# untitled.net
KiCad netlist of a schematic drawn in EAGLE
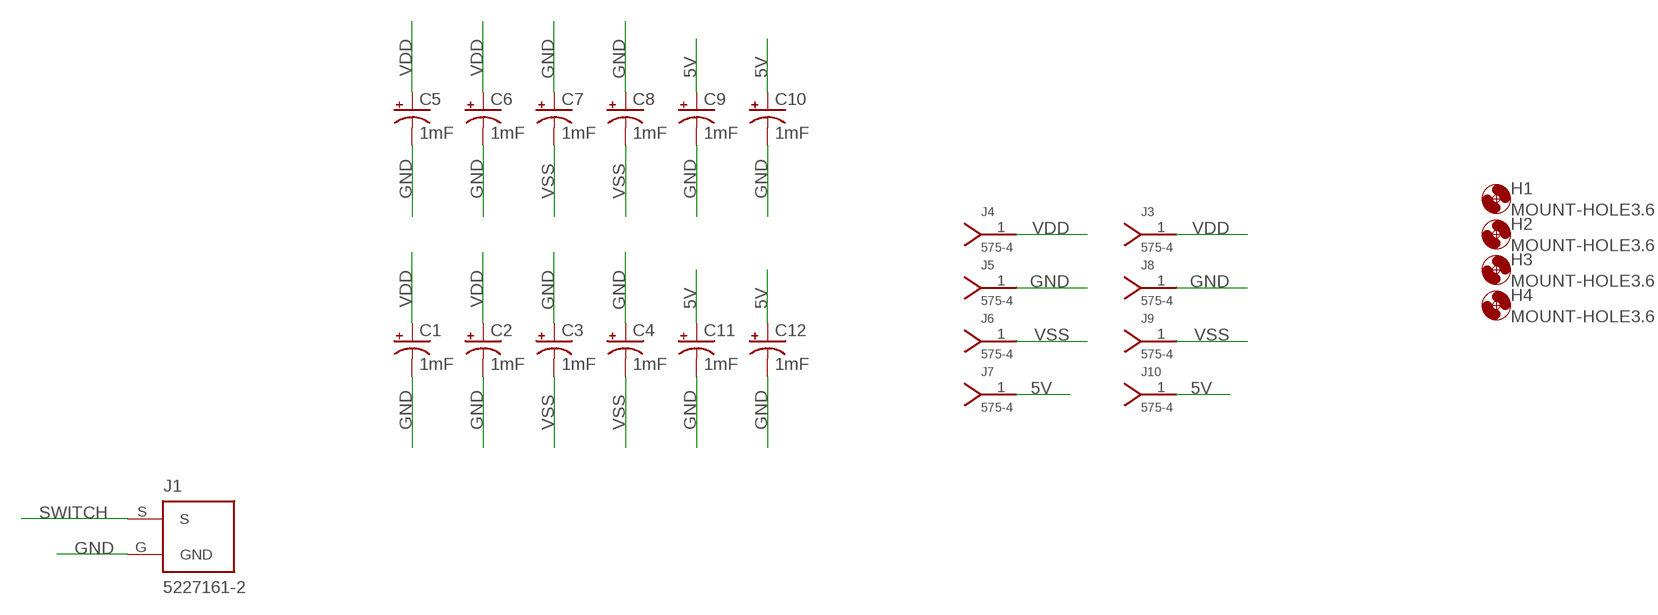
[diagram p0: schematic, sheet 1]
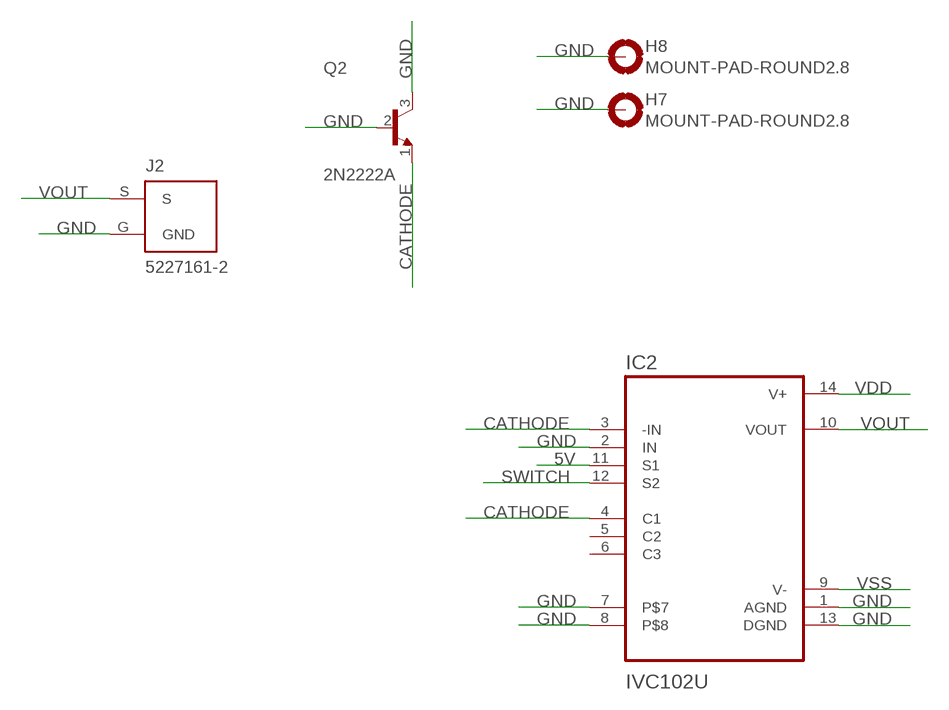
[diagram p1: schematic, sheet 2]
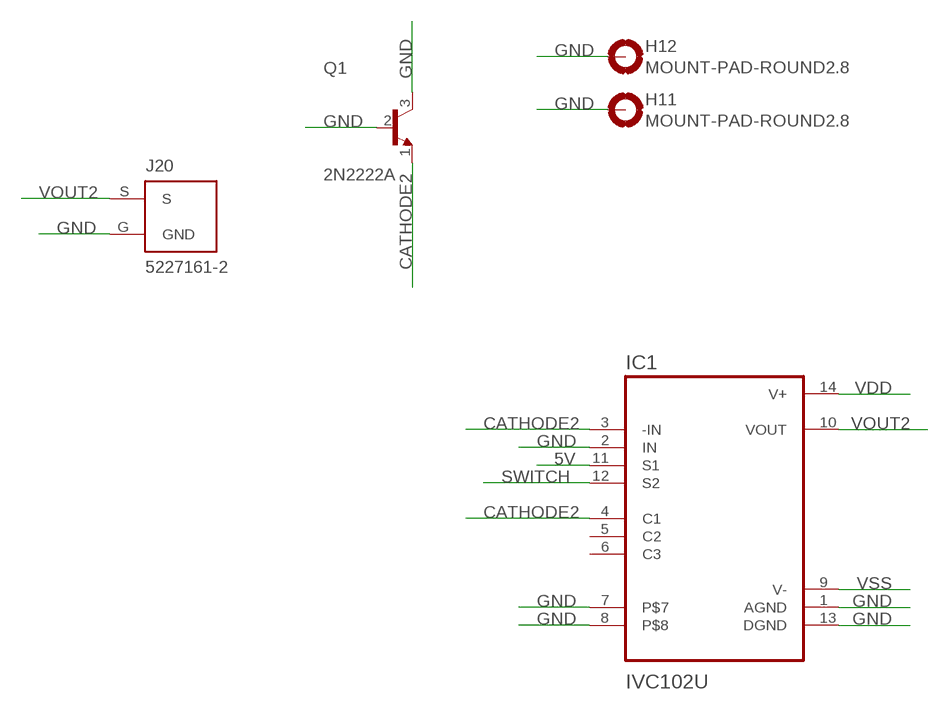
[diagram p2: schematic, sheet 3]
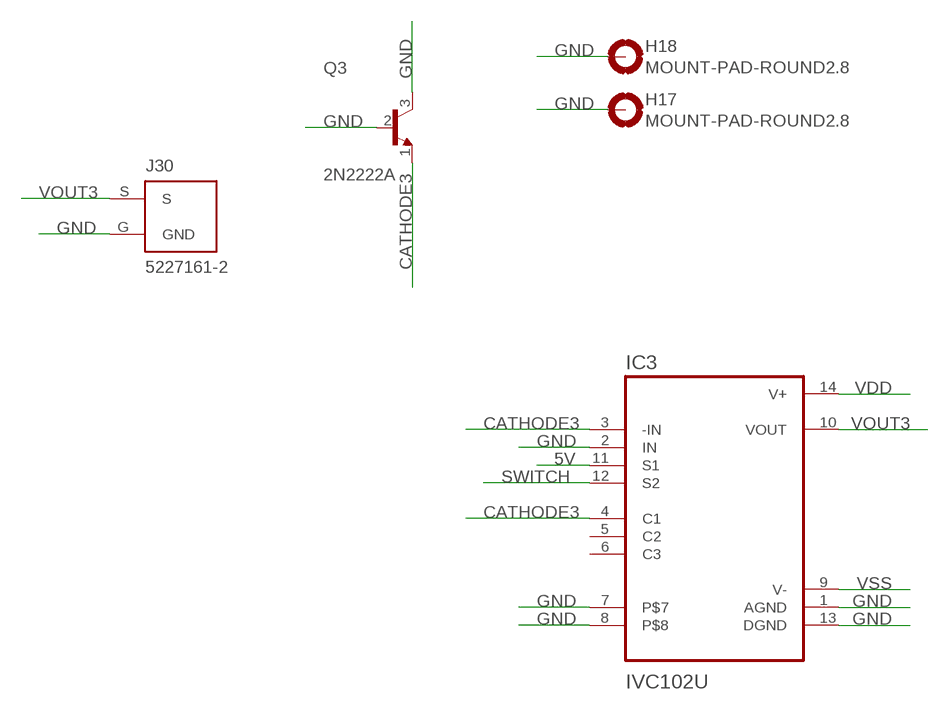
[diagram p3: schematic, sheet 4]
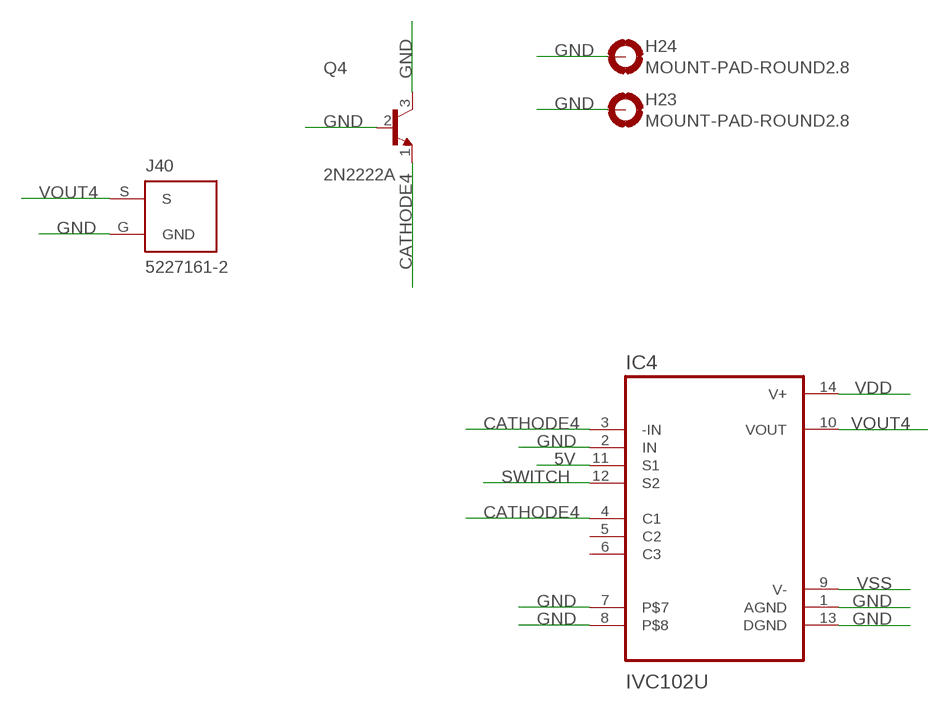
[diagram p4: schematic, sheet 5]

(export (version "E")
  (design (tool "Eeschema 10.0.6"))
  (components
    (comp (ref "H17")
      (value "MOUNT-PAD-ROUND2.8")
      (footprint "eagle-import:2,8-PAD")
      (libsource (lib "eagle-import") (part "MOUNT-PAD-ROUND2.8"))
    )
    (comp (ref "H18")
      (value "MOUNT-PAD-ROUND2.8")
      (footprint "eagle-import:2,8-PAD")
      (libsource (lib "eagle-import") (part "MOUNT-PAD-ROUND2.8"))
    )
    (comp (ref "IC3")
      (value "IVC102U")
      (footprint "eagle-import:SOIC127P600X175-14N")
      (fields (field (name "MF") "Texas"))
      (libsource (lib "eagle-import") (part "IVC102U"))
    )
    (comp (ref "J30")
      (value "5227161-2")
      (footprint "eagle-import:TE_5227161-2")
      (fields (field (name "DIGI-KEY_PART_NUMBER") "A32245-ND") (field (name "MF") "TE Connectivity"))
      (libsource (lib "eagle-import") (part "5227161-2"))
    )
    (comp (ref "Q3")
      (value "2N2222A")
      (footprint "eagle-import:TO127P584H533-3")
      (fields (field (name "MF") "ON Semiconductor"))
      (libsource (lib "eagle-import") (part "2N2222A"))
    )
    (comp (ref "H23")
      (value "MOUNT-PAD-ROUND2.8")
      (footprint "eagle-import:2,8-PAD")
      (libsource (lib "eagle-import") (part "MOUNT-PAD-ROUND2.8"))
    )
    (comp (ref "H24")
      (value "MOUNT-PAD-ROUND2.8")
      (footprint "eagle-import:2,8-PAD")
      (libsource (lib "eagle-import") (part "MOUNT-PAD-ROUND2.8"))
    )
    (comp (ref "IC4")
      (value "IVC102U")
      (footprint "eagle-import:SOIC127P600X175-14N")
      (fields (field (name "MF") "Texas"))
      (libsource (lib "eagle-import") (part "IVC102U"))
    )
    (comp (ref "J40")
      (value "5227161-2")
      (footprint "eagle-import:TE_5227161-2")
      (fields (field (name "DIGI-KEY_PART_NUMBER") "A32245-ND") (field (name "MF") "TE Connectivity"))
      (libsource (lib "eagle-import") (part "5227161-2"))
    )
    (comp (ref "Q4")
      (value "2N2222A")
      (footprint "eagle-import:TO127P584H533-3")
      (fields (field (name "MF") "ON Semiconductor"))
      (libsource (lib "eagle-import") (part "2N2222A"))
    )
    (comp (ref "H11")
      (value "MOUNT-PAD-ROUND2.8")
      (footprint "eagle-import:2,8-PAD")
      (libsource (lib "eagle-import") (part "MOUNT-PAD-ROUND2.8"))
    )
    (comp (ref "H12")
      (value "MOUNT-PAD-ROUND2.8")
      (footprint "eagle-import:2,8-PAD")
      (libsource (lib "eagle-import") (part "MOUNT-PAD-ROUND2.8"))
    )
    (comp (ref "IC1")
      (value "IVC102U")
      (footprint "eagle-import:SOIC127P600X175-14N")
      (fields (field (name "MF") "Texas"))
      (libsource (lib "eagle-import") (part "IVC102U"))
    )
    (comp (ref "J20")
      (value "5227161-2")
      (footprint "eagle-import:TE_5227161-2")
      (fields (field (name "DIGI-KEY_PART_NUMBER") "A32245-ND") (field (name "MF") "TE Connectivity"))
      (libsource (lib "eagle-import") (part "5227161-2"))
    )
    (comp (ref "Q1")
      (value "2N2222A")
      (footprint "eagle-import:TO127P584H533-3")
      (fields (field (name "MF") "ON Semiconductor"))
      (libsource (lib "eagle-import") (part "2N2222A"))
    )
    (comp (ref "H7")
      (value "MOUNT-PAD-ROUND2.8")
      (footprint "eagle-import:2,8-PAD")
      (libsource (lib "eagle-import") (part "MOUNT-PAD-ROUND2.8"))
    )
    (comp (ref "H8")
      (value "MOUNT-PAD-ROUND2.8")
      (footprint "eagle-import:2,8-PAD")
      (libsource (lib "eagle-import") (part "MOUNT-PAD-ROUND2.8"))
    )
    (comp (ref "IC2")
      (value "IVC102U")
      (footprint "eagle-import:SOIC127P600X175-14N")
      (fields (field (name "MF") "Texas"))
      (libsource (lib "eagle-import") (part "IVC102U"))
    )
    (comp (ref "J2")
      (value "5227161-2")
      (footprint "eagle-import:TE_5227161-2")
      (fields (field (name "DIGI-KEY_PART_NUMBER") "A32245-ND") (field (name "MF") "TE Connectivity"))
      (libsource (lib "eagle-import") (part "5227161-2"))
    )
    (comp (ref "Q2")
      (value "2N2222A")
      (footprint "eagle-import:TO127P584H533-3")
      (fields (field (name "MF") "ON Semiconductor"))
      (libsource (lib "eagle-import") (part "2N2222A"))
    )
    (comp (ref "C1")
      (value "1mF")
      (footprint "eagle-import:CPOL-RADIAL-5MM-10MM")
      (libsource (lib "eagle-import") (part "1000UF-RADIAL-5MM-25V-20%"))
    )
    (comp (ref "C2")
      (value "1mF")
      (footprint "eagle-import:CPOL-RADIAL-5MM-10MM")
      (libsource (lib "eagle-import") (part "1000UF-RADIAL-5MM-25V-20%"))
    )
    (comp (ref "C3")
      (value "1mF")
      (footprint "eagle-import:CPOL-RADIAL-5MM-10MM")
      (libsource (lib "eagle-import") (part "1000UF-RADIAL-5MM-25V-20%"))
    )
    (comp (ref "C4")
      (value "1mF")
      (footprint "eagle-import:CPOL-RADIAL-5MM-10MM")
      (libsource (lib "eagle-import") (part "1000UF-RADIAL-5MM-25V-20%"))
    )
    (comp (ref "C5")
      (value "1mF")
      (footprint "eagle-import:CPOL-RADIAL-5MM-10MM")
      (libsource (lib "eagle-import") (part "1000UF-RADIAL-5MM-25V-20%"))
    )
    (comp (ref "C6")
      (value "1mF")
      (footprint "eagle-import:CPOL-RADIAL-5MM-10MM")
      (libsource (lib "eagle-import") (part "1000UF-RADIAL-5MM-25V-20%"))
    )
    (comp (ref "C7")
      (value "1mF")
      (footprint "eagle-import:CPOL-RADIAL-5MM-10MM")
      (libsource (lib "eagle-import") (part "1000UF-RADIAL-5MM-25V-20%"))
    )
    (comp (ref "C8")
      (value "1mF")
      (footprint "eagle-import:CPOL-RADIAL-5MM-10MM")
      (libsource (lib "eagle-import") (part "1000UF-RADIAL-5MM-25V-20%"))
    )
    (comp (ref "C9")
      (value "1mF")
      (footprint "eagle-import:CPOL-RADIAL-5MM-10MM")
      (libsource (lib "eagle-import") (part "1000UF-RADIAL-5MM-25V-20%"))
    )
    (comp (ref "C10")
      (value "1mF")
      (footprint "eagle-import:CPOL-RADIAL-5MM-10MM")
      (libsource (lib "eagle-import") (part "1000UF-RADIAL-5MM-25V-20%"))
    )
    (comp (ref "C11")
      (value "1mF")
      (footprint "eagle-import:CPOL-RADIAL-5MM-10MM")
      (libsource (lib "eagle-import") (part "1000UF-RADIAL-5MM-25V-20%"))
    )
    (comp (ref "C12")
      (value "1mF")
      (footprint "eagle-import:CPOL-RADIAL-5MM-10MM")
      (libsource (lib "eagle-import") (part "1000UF-RADIAL-5MM-25V-20%"))
    )
    (comp (ref "H1")
      (value "MOUNT-HOLE3.6")
      (footprint "eagle-import:3,6")
      (libsource (lib "eagle-import") (part "MOUNT-HOLE3.6"))
    )
    (comp (ref "H2")
      (value "MOUNT-HOLE3.6")
      (footprint "eagle-import:3,6")
      (libsource (lib "eagle-import") (part "MOUNT-HOLE3.6"))
    )
    (comp (ref "H3")
      (value "MOUNT-HOLE3.6")
      (footprint "eagle-import:3,6")
      (libsource (lib "eagle-import") (part "MOUNT-HOLE3.6"))
    )
    (comp (ref "H4")
      (value "MOUNT-HOLE3.6")
      (footprint "eagle-import:3,6")
      (libsource (lib "eagle-import") (part "MOUNT-HOLE3.6"))
    )
    (comp (ref "J1")
      (value "5227161-2")
      (footprint "eagle-import:TE_5227161-2")
      (fields (field (name "DIGI-KEY_PART_NUMBER") "A32245-ND") (field (name "MF") "TE Connectivity"))
      (libsource (lib "eagle-import") (part "5227161-2"))
    )
    (comp (ref "J3")
      (value "575-4")
      (footprint "eagle-import:KEYSTONE_575-4")
      (fields (field (name "DIGI-KEY_PART_NUMBER") "36-575-4-ND") (field (name "MF") "Keystone Electronics"))
      (libsource (lib "eagle-import") (part "575-4"))
    )
    (comp (ref "J4")
      (value "575-4")
      (footprint "eagle-import:KEYSTONE_575-4")
      (fields (field (name "DIGI-KEY_PART_NUMBER") "36-575-4-ND") (field (name "MF") "Keystone Electronics"))
      (libsource (lib "eagle-import") (part "575-4"))
    )
    (comp (ref "J5")
      (value "575-4")
      (footprint "eagle-import:KEYSTONE_575-4")
      (fields (field (name "DIGI-KEY_PART_NUMBER") "36-575-4-ND") (field (name "MF") "Keystone Electronics"))
      (libsource (lib "eagle-import") (part "575-4"))
    )
    (comp (ref "J6")
      (value "575-4")
      (footprint "eagle-import:KEYSTONE_575-4")
      (fields (field (name "DIGI-KEY_PART_NUMBER") "36-575-4-ND") (field (name "MF") "Keystone Electronics"))
      (libsource (lib "eagle-import") (part "575-4"))
    )
    (comp (ref "J7")
      (value "575-4")
      (footprint "eagle-import:KEYSTONE_575-4")
      (fields (field (name "DIGI-KEY_PART_NUMBER") "36-575-4-ND") (field (name "MF") "Keystone Electronics"))
      (libsource (lib "eagle-import") (part "575-4"))
    )
    (comp (ref "J8")
      (value "575-4")
      (footprint "eagle-import:KEYSTONE_575-4")
      (fields (field (name "DIGI-KEY_PART_NUMBER") "36-575-4-ND") (field (name "MF") "Keystone Electronics"))
      (libsource (lib "eagle-import") (part "575-4"))
    )
    (comp (ref "J9")
      (value "575-4")
      (footprint "eagle-import:KEYSTONE_575-4")
      (fields (field (name "DIGI-KEY_PART_NUMBER") "36-575-4-ND") (field (name "MF") "Keystone Electronics"))
      (libsource (lib "eagle-import") (part "575-4"))
    )
    (comp (ref "J10")
      (value "575-4")
      (footprint "eagle-import:KEYSTONE_575-4")
      (fields (field (name "DIGI-KEY_PART_NUMBER") "36-575-4-ND") (field (name "MF") "Keystone Electronics"))
      (libsource (lib "eagle-import") (part "575-4"))
    )
  )
  (nets
    (net (code "1") (name "5V") (class "Default")
      (node (ref "C10") (pin "+") (pinfunction "+_+") (pintype "passive"))
      (node (ref "C11") (pin "+") (pinfunction "+_+") (pintype "passive"))
      (node (ref "C12") (pin "+") (pinfunction "+_+") (pintype "passive"))
      (node (ref "C9") (pin "+") (pinfunction "+_+") (pintype "passive"))
      (node (ref "IC1") (pin "11") (pinfunction "S1_11") (pintype "input"))
      (node (ref "IC2") (pin "11") (pinfunction "S1_11") (pintype "input"))
      (node (ref "IC3") (pin "11") (pinfunction "S1_11") (pintype "input"))
      (node (ref "IC4") (pin "11") (pinfunction "S1_11") (pintype "input"))
      (node (ref "J10") (pin "1") (pinfunction "1_1") (pintype "passive"))
      (node (ref "J7") (pin "1") (pinfunction "1_1") (pintype "passive"))
    )
    (net (code "2") (name "CATHODE") (class "Default")
      (node (ref "IC2") (pin "3") (pinfunction "-IN_3") (pintype "input"))
      (node (ref "IC2") (pin "4") (pinfunction "C1_4") (pintype "bidirectional"))
      (node (ref "Q2") (pin "1") (pinfunction "E_1") (pintype "passive"))
    )
    (net (code "3") (name "CATHODE2") (class "Default")
      (node (ref "IC1") (pin "3") (pinfunction "-IN_3") (pintype "input"))
      (node (ref "IC1") (pin "4") (pinfunction "C1_4") (pintype "bidirectional"))
      (node (ref "Q1") (pin "1") (pinfunction "E_1") (pintype "passive"))
    )
    (net (code "4") (name "CATHODE3") (class "Default")
      (node (ref "IC3") (pin "3") (pinfunction "-IN_3") (pintype "input"))
      (node (ref "IC3") (pin "4") (pinfunction "C1_4") (pintype "bidirectional"))
      (node (ref "Q3") (pin "1") (pinfunction "E_1") (pintype "passive"))
    )
    (net (code "5") (name "CATHODE4") (class "Default")
      (node (ref "IC4") (pin "3") (pinfunction "-IN_3") (pintype "input"))
      (node (ref "IC4") (pin "4") (pinfunction "C1_4") (pintype "bidirectional"))
      (node (ref "Q4") (pin "1") (pinfunction "E_1") (pintype "passive"))
    )
    (net (code "6") (name "GND") (class "Default")
      (node (ref "C1") (pin "-") (pinfunction "-_-") (pintype "passive"))
      (node (ref "C10") (pin "-") (pinfunction "-_-") (pintype "passive"))
      (node (ref "C11") (pin "-") (pinfunction "-_-") (pintype "passive"))
      (node (ref "C12") (pin "-") (pinfunction "-_-") (pintype "passive"))
      (node (ref "C2") (pin "-") (pinfunction "-_-") (pintype "passive"))
      (node (ref "C3") (pin "+") (pinfunction "+_+") (pintype "passive"))
      (node (ref "C4") (pin "+") (pinfunction "+_+") (pintype "passive"))
      (node (ref "C5") (pin "-") (pinfunction "-_-") (pintype "passive"))
      (node (ref "C6") (pin "-") (pinfunction "-_-") (pintype "passive"))
      (node (ref "C7") (pin "+") (pinfunction "+_+") (pintype "passive"))
      (node (ref "C8") (pin "+") (pinfunction "+_+") (pintype "passive"))
      (node (ref "C9") (pin "-") (pinfunction "-_-") (pintype "passive"))
      (node (ref "H11") (pin "B2,8") (pinfunction "MOUNT_B2,8") (pintype "passive"))
      (node (ref "H12") (pin "B2,8") (pinfunction "MOUNT_B2,8") (pintype "passive"))
      (node (ref "H17") (pin "B2,8") (pinfunction "MOUNT_B2,8") (pintype "passive"))
      (node (ref "H18") (pin "B2,8") (pinfunction "MOUNT_B2,8") (pintype "passive"))
      (node (ref "H23") (pin "B2,8") (pinfunction "MOUNT_B2,8") (pintype "passive"))
      (node (ref "H24") (pin "B2,8") (pinfunction "MOUNT_B2,8") (pintype "passive"))
      (node (ref "H7") (pin "B2,8") (pinfunction "MOUNT_B2,8") (pintype "passive"))
      (node (ref "H8") (pin "B2,8") (pinfunction "MOUNT_B2,8") (pintype "passive"))
      (node (ref "IC1") (pin "1") (pinfunction "AGND_1") (pintype "power_in"))
      (node (ref "IC1") (pin "13") (pinfunction "DGND_13") (pintype "power_in"))
      (node (ref "IC1") (pin "2") (pinfunction "IN_2") (pintype "input"))
      (node (ref "IC1") (pin "7") (pinfunction "P$7_7") (pintype "bidirectional"))
      (node (ref "IC1") (pin "8") (pinfunction "P$8_8") (pintype "bidirectional"))
      (node (ref "IC2") (pin "1") (pinfunction "AGND_1") (pintype "power_in"))
      (node (ref "IC2") (pin "13") (pinfunction "DGND_13") (pintype "power_in"))
      (node (ref "IC2") (pin "2") (pinfunction "IN_2") (pintype "input"))
      (node (ref "IC2") (pin "7") (pinfunction "P$7_7") (pintype "bidirectional"))
      (node (ref "IC2") (pin "8") (pinfunction "P$8_8") (pintype "bidirectional"))
      (node (ref "IC3") (pin "1") (pinfunction "AGND_1") (pintype "power_in"))
      (node (ref "IC3") (pin "13") (pinfunction "DGND_13") (pintype "power_in"))
      (node (ref "IC3") (pin "2") (pinfunction "IN_2") (pintype "input"))
      (node (ref "IC3") (pin "7") (pinfunction "P$7_7") (pintype "bidirectional"))
      (node (ref "IC3") (pin "8") (pinfunction "P$8_8") (pintype "bidirectional"))
      (node (ref "IC4") (pin "1") (pinfunction "AGND_1") (pintype "power_in"))
      (node (ref "IC4") (pin "13") (pinfunction "DGND_13") (pintype "power_in"))
      (node (ref "IC4") (pin "2") (pinfunction "IN_2") (pintype "input"))
      (node (ref "IC4") (pin "7") (pinfunction "P$7_7") (pintype "bidirectional"))
      (node (ref "IC4") (pin "8") (pinfunction "P$8_8") (pintype "bidirectional"))
      (node (ref "J1") (pin "G") (pinfunction "GND_G") (pintype "power_in"))
      (node (ref "J2") (pin "G") (pinfunction "GND_G") (pintype "power_in"))
      (node (ref "J20") (pin "G") (pinfunction "GND_G") (pintype "power_in"))
      (node (ref "J30") (pin "G") (pinfunction "GND_G") (pintype "power_in"))
      (node (ref "J40") (pin "G") (pinfunction "GND_G") (pintype "power_in"))
      (node (ref "J5") (pin "1") (pinfunction "1_1") (pintype "passive"))
      (node (ref "J8") (pin "1") (pinfunction "1_1") (pintype "passive"))
      (node (ref "Q1") (pin "2") (pinfunction "B_2") (pintype "passive"))
      (node (ref "Q1") (pin "3") (pinfunction "C_3") (pintype "passive"))
      (node (ref "Q2") (pin "2") (pinfunction "B_2") (pintype "passive"))
      (node (ref "Q2") (pin "3") (pinfunction "C_3") (pintype "passive"))
      (node (ref "Q3") (pin "2") (pinfunction "B_2") (pintype "passive"))
      (node (ref "Q3") (pin "3") (pinfunction "C_3") (pintype "passive"))
      (node (ref "Q4") (pin "2") (pinfunction "B_2") (pintype "passive"))
      (node (ref "Q4") (pin "3") (pinfunction "C_3") (pintype "passive"))
    )
    (net (code "7") (name "SWITCH") (class "Default")
      (node (ref "IC1") (pin "12") (pinfunction "S2_12") (pintype "input"))
      (node (ref "IC2") (pin "12") (pinfunction "S2_12") (pintype "input"))
      (node (ref "IC3") (pin "12") (pinfunction "S2_12") (pintype "input"))
      (node (ref "IC4") (pin "12") (pinfunction "S2_12") (pintype "input"))
      (node (ref "J1") (pin "S") (pinfunction "S_S") (pintype "passive"))
    )
    (net (code "8") (name "VDD") (class "Default")
      (node (ref "C1") (pin "+") (pinfunction "+_+") (pintype "passive"))
      (node (ref "C2") (pin "+") (pinfunction "+_+") (pintype "passive"))
      (node (ref "C5") (pin "+") (pinfunction "+_+") (pintype "passive"))
      (node (ref "C6") (pin "+") (pinfunction "+_+") (pintype "passive"))
      (node (ref "IC1") (pin "14") (pinfunction "V+_14") (pintype "power_in"))
      (node (ref "IC2") (pin "14") (pinfunction "V+_14") (pintype "power_in"))
      (node (ref "IC3") (pin "14") (pinfunction "V+_14") (pintype "power_in"))
      (node (ref "IC4") (pin "14") (pinfunction "V+_14") (pintype "power_in"))
      (node (ref "J3") (pin "1") (pinfunction "1_1") (pintype "passive"))
      (node (ref "J4") (pin "1") (pinfunction "1_1") (pintype "passive"))
    )
    (net (code "9") (name "VOUT") (class "Default")
      (node (ref "IC2") (pin "10") (pinfunction "VOUT_10") (pintype "output"))
      (node (ref "J2") (pin "S") (pinfunction "S_S") (pintype "passive"))
    )
    (net (code "10") (name "VOUT2") (class "Default")
      (node (ref "IC1") (pin "10") (pinfunction "VOUT_10") (pintype "output"))
      (node (ref "J20") (pin "S") (pinfunction "S_S") (pintype "passive"))
    )
    (net (code "11") (name "VOUT3") (class "Default")
      (node (ref "IC3") (pin "10") (pinfunction "VOUT_10") (pintype "output"))
      (node (ref "J30") (pin "S") (pinfunction "S_S") (pintype "passive"))
    )
    (net (code "12") (name "VOUT4") (class "Default")
      (node (ref "IC4") (pin "10") (pinfunction "VOUT_10") (pintype "output"))
      (node (ref "J40") (pin "S") (pinfunction "S_S") (pintype "passive"))
    )
    (net (code "13") (name "VSS") (class "Default")
      (node (ref "C3") (pin "-") (pinfunction "-_-") (pintype "passive"))
      (node (ref "C4") (pin "-") (pinfunction "-_-") (pintype "passive"))
      (node (ref "C7") (pin "-") (pinfunction "-_-") (pintype "passive"))
      (node (ref "C8") (pin "-") (pinfunction "-_-") (pintype "passive"))
      (node (ref "IC1") (pin "9") (pinfunction "V-_9") (pintype "power_in"))
      (node (ref "IC2") (pin "9") (pinfunction "V-_9") (pintype "power_in"))
      (node (ref "IC3") (pin "9") (pinfunction "V-_9") (pintype "power_in"))
      (node (ref "IC4") (pin "9") (pinfunction "V-_9") (pintype "power_in"))
      (node (ref "J6") (pin "1") (pinfunction "1_1") (pintype "passive"))
      (node (ref "J9") (pin "1") (pinfunction "1_1") (pintype "passive"))
    )
    (net (code "14") (name "unconnected-(IC1-C2-Pad5)") (class "Default")
      (node (ref "IC1") (pin "5") (pinfunction "C2_5") (pintype "bidirectional"))
    )
    (net (code "15") (name "unconnected-(IC1-C3-Pad6)") (class "Default")
      (node (ref "IC1") (pin "6") (pinfunction "C3_6") (pintype "bidirectional"))
    )
    (net (code "16") (name "unconnected-(IC2-C2-Pad5)") (class "Default")
      (node (ref "IC2") (pin "5") (pinfunction "C2_5") (pintype "bidirectional"))
    )
    (net (code "17") (name "unconnected-(IC2-C3-Pad6)") (class "Default")
      (node (ref "IC2") (pin "6") (pinfunction "C3_6") (pintype "bidirectional"))
    )
    (net (code "18") (name "unconnected-(IC3-C2-Pad5)") (class "Default")
      (node (ref "IC3") (pin "5") (pinfunction "C2_5") (pintype "bidirectional"))
    )
    (net (code "19") (name "unconnected-(IC3-C3-Pad6)") (class "Default")
      (node (ref "IC3") (pin "6") (pinfunction "C3_6") (pintype "bidirectional"))
    )
    (net (code "20") (name "unconnected-(IC4-C2-Pad5)") (class "Default")
      (node (ref "IC4") (pin "5") (pinfunction "C2_5") (pintype "bidirectional"))
    )
    (net (code "21") (name "unconnected-(IC4-C3-Pad6)") (class "Default")
      (node (ref "IC4") (pin "6") (pinfunction "C3_6") (pintype "bidirectional"))
    )
  )
)
